# I2C_DP_Sensor_2.net
KiCad netlist of a schematic drawn in Altium Designer
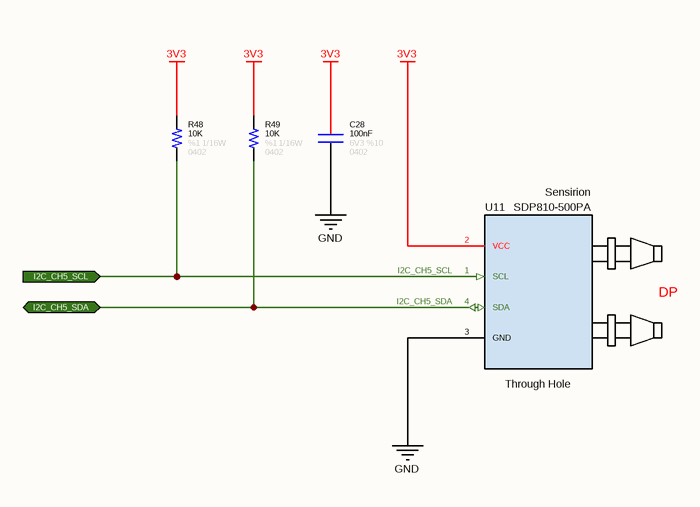
[diagram p0: I2C DP Sensor 2.SchDoc]

(export (version "E")
  (design (tool "Eeschema 10.0.6"))
  (components
    (comp (ref "C28")
      (value "100nF")
      (footprint "CAPACITOR_0402")
      (description "Capacitor - 100nF [0402-6V3] (Ceramic)")
      (fields
        (field (name "MANUFACTURER PART NUMBER") "04026D104KAT4A")
        (field (name "TOLERANCE") "%10")
        (field (name "VOLTAGE") "6V3")
        (field (name "CASE") "0402")
        (field (name "Comment") "Capacitor - 100nF [0402] (Ceramic)")
      )
      (libsource (lib "Akkoyun") (part "Capacitor - 100nF [0402-6V3]"))
    )
    (comp (ref "R48")
      (value "10K")
      (footprint "RESISTOR_0402")
      (description "Thick Film Resistors - SMD 1/16 W 10 KOhm 1%")
      (fields
        (field (name "MANUFACTURER PART NUMBER") "CRCW040210K0FKED")
        (field (name "TOLERANCE") "%1")
        (field (name "CASE") "0402")
        (field (name "POWER") "1/16W")
        (field (name "Comment") "10K - 0402 - %1 - 1/16W")
      )
      (libsource (lib "Akkoyun") (part "Resistor - 10K [0402]"))
    )
    (comp (ref "R49")
      (value "10K")
      (footprint "RESISTOR_0402")
      (description "Thick Film Resistors - SMD 1/16 W 10 KOhm 1%")
      (fields
        (field (name "MANUFACTURER PART NUMBER") "CRCW040210K0FKED")
        (field (name "TOLERANCE") "%1")
        (field (name "CASE") "0402")
        (field (name "POWER") "1/16W")
        (field (name "Comment") "10K - 0402 - %1 - 1/16W")
      )
      (libsource (lib "Akkoyun") (part "Resistor - 10K [0402]"))
    )
    (comp (ref "U11")
      (value "SDP810-500PA")
      (footprint "SDP810-500PA")
      (description "Board Mount Pressure Sensors Tube Connection, I2C , 500Pa")
      (fields
        (field (name "MANUFACTURER NAME") "Sensirion")
        (field (name "MANUFACTURER PART NUMBER") "SDP810-500PA")
        (field (name "CASE") "Through Hole")
      )
      (libsource (lib "Akkoyun") (part "IC - SDP810-500PA"))
    )
  )
  (nets
    (net (code "1") (name "/I2C_CH5_SCL") (class "Default")
      (node (ref "R48") (pin "1") (pinfunction "1_1") (pintype "passive"))
      (node (ref "U11") (pin "1") (pinfunction "SCL_1") (pintype "input"))
    )
    (net (code "2") (name "/I2C_CH5_SDA") (class "Default")
      (node (ref "R49") (pin "1") (pinfunction "1_1") (pintype "passive"))
      (node (ref "U11") (pin "4") (pinfunction "SDA_4") (pintype "bidirectional"))
    )
    (net (code "3") (name "3V3") (class "Default")
      (node (ref "C28") (pin "2") (pinfunction "2_2") (pintype "passive"))
      (node (ref "R48") (pin "2") (pinfunction "2_2") (pintype "passive"))
      (node (ref "R49") (pin "2") (pinfunction "2_2") (pintype "passive"))
      (node (ref "U11") (pin "2") (pinfunction "VCC_2") (pintype "power_in"))
    )
    (net (code "4") (name "GND") (class "Default")
      (node (ref "C28") (pin "1") (pinfunction "1_1") (pintype "passive"))
      (node (ref "U11") (pin "3") (pinfunction "GND_3") (pintype "passive"))
    )
  )
)
